# FTIR_v0_1_noCC2.net
KiCad netlist of a schematic drawn in EAGLE
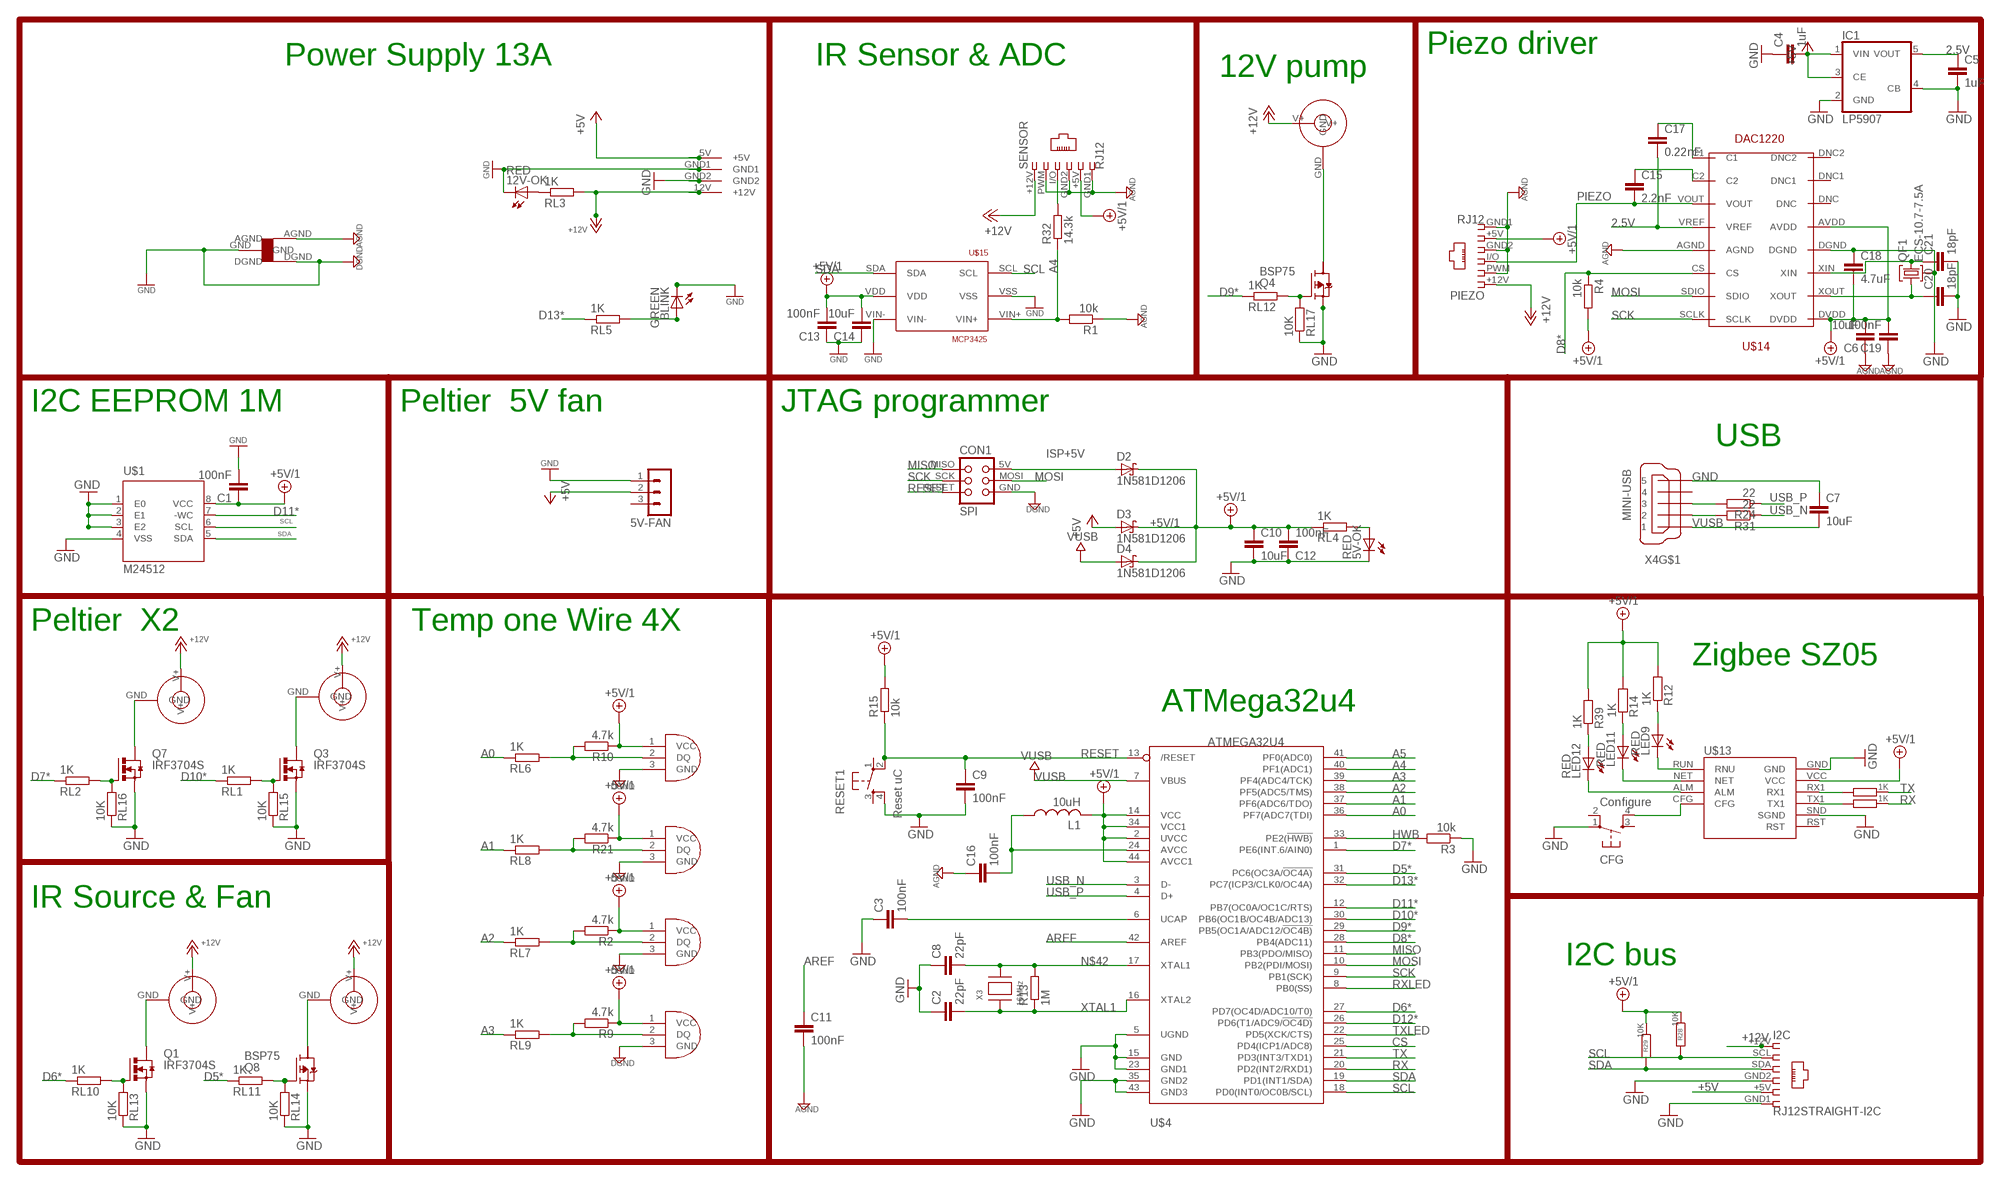
[diagram p0: schematic, sheet 1, part 1 of 2]
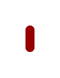
[diagram p1: schematic, sheet 1, part 2 of 2]

(export (version "E")
  (design (tool "Eeschema 10.0.6"))
  (components
    (comp (ref "5V-FAN")
      (value "MA03-1")
      (footprint "eagle-import:MA03-1")
      (libsource (lib "eagle-import") (part "MA03-1"))
    )
    (comp (ref "5V-OK")
      (value "RED")
      (footprint "eagle-import:CHIPLED_1206")
      (libsource (lib "eagle-import") (part "LEDCHIPLED_1206"))
    )
    (comp (ref "12V-OK")
      (value "RED")
      (footprint "eagle-import:CHIPLED_1206")
      (libsource (lib "eagle-import") (part "LEDCHIPLED_1206"))
    )
    (comp (ref "BLINK")
      (value "GREEN")
      (footprint "eagle-import:CHIPLED_1206")
      (libsource (lib "eagle-import") (part "LEDCHIPLED_1206"))
    )
    (comp (ref "C1")
      (value "100nF")
      (footprint "eagle-import:C1206")
      (libsource (lib "eagle-import") (part "C-EUC1206"))
    )
    (comp (ref "C2")
      (value "22pF")
      (footprint "eagle-import:C1206")
      (libsource (lib "eagle-import") (part "C-EUC1206"))
    )
    (comp (ref "C3")
      (value "100nF")
      (footprint "eagle-import:C1206")
      (libsource (lib "eagle-import") (part "C-EUC1206"))
    )
    (comp (ref "C4")
      (value "1uF")
      (footprint "eagle-import:C1206")
      (libsource (lib "eagle-import") (part "C-EUC1206"))
    )
    (comp (ref "C5")
      (value "1uF")
      (footprint "eagle-import:C1206")
      (libsource (lib "eagle-import") (part "C-EUC1206"))
    )
    (comp (ref "C6")
      (value "10uF")
      (footprint "eagle-import:C1206")
      (libsource (lib "eagle-import") (part "C-EUC1206"))
    )
    (comp (ref "C7")
      (value "10uF")
      (footprint "eagle-import:C1206")
      (libsource (lib "eagle-import") (part "C-EUC1206"))
    )
    (comp (ref "C8")
      (value "22pF")
      (footprint "eagle-import:C1206")
      (libsource (lib "eagle-import") (part "C-EUC1206"))
    )
    (comp (ref "C9")
      (value "100nF")
      (footprint "eagle-import:C1206")
      (libsource (lib "eagle-import") (part "C-EUC1206"))
    )
    (comp (ref "C10")
      (value "10uF")
      (footprint "eagle-import:C1206")
      (libsource (lib "eagle-import") (part "C-EUC1206"))
    )
    (comp (ref "C11")
      (value "100nF")
      (footprint "eagle-import:C1206")
      (libsource (lib "eagle-import") (part "C-EUC1206"))
    )
    (comp (ref "C12")
      (value "100nF")
      (footprint "eagle-import:C1206")
      (libsource (lib "eagle-import") (part "C-EUC1206"))
    )
    (comp (ref "C13")
      (value "100nF")
      (footprint "eagle-import:C1206")
      (libsource (lib "eagle-import") (part "C-EUC1206"))
    )
    (comp (ref "C14")
      (value "10uF")
      (footprint "eagle-import:C1206")
      (libsource (lib "eagle-import") (part "C-EUC1206"))
    )
    (comp (ref "C15")
      (value "2.2nF")
      (footprint "eagle-import:C1206")
      (libsource (lib "eagle-import") (part "C-EUC1206"))
    )
    (comp (ref "C16")
      (value "100nF")
      (footprint "eagle-import:C1206")
      (libsource (lib "eagle-import") (part "C-EUC1206"))
    )
    (comp (ref "C17")
      (value "0.22nF")
      (footprint "eagle-import:C1206")
      (libsource (lib "eagle-import") (part "C-EUC1206"))
    )
    (comp (ref "C18")
      (value "4.7uF")
      (footprint "eagle-import:C1206")
      (libsource (lib "eagle-import") (part "C-EUC1206"))
    )
    (comp (ref "C19")
      (value "100nF")
      (footprint "eagle-import:C1206")
      (libsource (lib "eagle-import") (part "C-EUC1206"))
    )
    (comp (ref "C20")
      (value "18pF")
      (footprint "eagle-import:C1206")
      (libsource (lib "eagle-import") (part "C-EUC1206"))
    )
    (comp (ref "C21")
      (value "18pF")
      (footprint "eagle-import:C1206")
      (libsource (lib "eagle-import") (part "C-EUC1206"))
    )
    (comp (ref "CFG")
      (value "Configure")
      (footprint "eagle-import:TACTILE_SWITCH_SMD")
      (libsource (lib "eagle-import") (part "TAC_SWITCHSMD"))
    )
    (comp (ref "CON1")
      (value "SPI")
      (footprint "eagle-import:TC2030-MCP-NL")
      (libsource (lib "eagle-import") (part "TINYISPT"))
    )
    (comp (ref "D2")
      (value "1N581D1206")
      (footprint "eagle-import:LED-1206")
      (libsource (lib "eagle-import") (part "1N581D1206"))
    )
    (comp (ref "D3")
      (value "1N581D1206")
      (footprint "eagle-import:LED-1206")
      (libsource (lib "eagle-import") (part "1N581D1206"))
    )
    (comp (ref "D4")
      (value "1N581D1206")
      (footprint "eagle-import:LED-1206")
      (libsource (lib "eagle-import") (part "1N581D1206"))
    )
    (comp (ref "I2C")
      (value "RJ12STRAIGHT-I2C")
      (footprint "eagle-import:RJ12-STRAIGHT-I2C")
      (libsource (lib "eagle-import") (part "RJ12STRAIGHT-I2C"))
    )
    (comp (ref "IC1")
      (value "LP5907")
      (footprint "eagle-import:SOT25")
      (libsource (lib "eagle-import") (part "TS520525"))
    )
    (comp (ref "L1")
      (value "10uH")
      (footprint "eagle-import:L2012C")
      (libsource (lib "eagle-import") (part "L-USL2012C"))
    )
    (comp (ref "LED9")
      (value "RED")
      (footprint "eagle-import:CHIPLED_1206")
      (libsource (lib "eagle-import") (part "LEDCHIPLED_1206"))
    )
    (comp (ref "LED11")
      (value "RED")
      (footprint "eagle-import:CHIPLED_1206")
      (libsource (lib "eagle-import") (part "LEDCHIPLED_1206"))
    )
    (comp (ref "LED12")
      (value "RED")
      (footprint "eagle-import:CHIPLED_1206")
      (libsource (lib "eagle-import") (part "LEDCHIPLED_1206"))
    )
    (comp (ref "PIEZO")
      (value "RJ12")
      (footprint "eagle-import:RJ12-STRAIGHT")
      (libsource (lib "eagle-import") (part "RJ12STRAIGHT"))
    )
    (comp (ref "Q1")
      (value "IRF3704S")
      (footprint "eagle-import:D2PACK")
      (libsource (lib "eagle-import") (part "IRF3704S"))
    )
    (comp (ref "Q3")
      (value "IRF3704S")
      (footprint "eagle-import:D2PACK")
      (libsource (lib "eagle-import") (part "IRF3704S"))
    )
    (comp (ref "Q4")
      (value "BSP75")
      (footprint "eagle-import:PG-SOT-223")
      (libsource (lib "eagle-import") (part "BSP613P"))
    )
    (comp (ref "Q7")
      (value "IRF3704S")
      (footprint "eagle-import:D2PACK")
      (libsource (lib "eagle-import") (part "IRF3704S"))
    )
    (comp (ref "Q8")
      (value "BSP75")
      (footprint "eagle-import:PG-SOT-223")
      (libsource (lib "eagle-import") (part "BSP613P"))
    )
    (comp (ref "QF1")
      (value "ECS-10.7-7.5A")
      (footprint "eagle-import:HC49U")
      (libsource (lib "eagle-import") (part "ECS-10.7-7.5A"))
    )
    (comp (ref "R1")
      (value "10k")
      (footprint "eagle-import:R0805")
      (libsource (lib "eagle-import") (part "R-EU_R0805"))
    )
    (comp (ref "R2")
      (value "4.7k")
      (footprint "eagle-import:R1206")
      (libsource (lib "eagle-import") (part "resistor_R-EU_R1206"))
    )
    (comp (ref "R3")
      (value "10k")
      (footprint "eagle-import:M0805")
      (libsource (lib "eagle-import") (part "resistor_R-EU_M0805"))
    )
    (comp (ref "R4")
      (value "10k")
      (footprint "eagle-import:R0805")
      (libsource (lib "eagle-import") (part "R-EU_R0805"))
    )
    (comp (ref "R8")
      (value "1K")
      (footprint "eagle-import:R0805")
      (libsource (lib "eagle-import") (part "R-EU_R0805"))
    )
    (comp (ref "R9")
      (value "4.7k")
      (footprint "eagle-import:R1206")
      (libsource (lib "eagle-import") (part "resistor_R-EU_R1206"))
    )
    (comp (ref "R10")
      (value "4.7k")
      (footprint "eagle-import:R1206")
      (libsource (lib "eagle-import") (part "resistor_R-EU_R1206"))
    )
    (comp (ref "R11")
      (value "1K")
      (footprint "eagle-import:R0805")
      (libsource (lib "eagle-import") (part "R-EU_R0805"))
    )
    (comp (ref "R12")
      (value "1K")
      (footprint "eagle-import:R0805")
      (libsource (lib "eagle-import") (part "R-EU_R0805"))
    )
    (comp (ref "R13")
      (value "1M")
      (footprint "eagle-import:R1206")
      (libsource (lib "eagle-import") (part "R-EU_R1206"))
    )
    (comp (ref "R14")
      (value "1K")
      (footprint "eagle-import:R0805")
      (libsource (lib "eagle-import") (part "R-EU_R0805"))
    )
    (comp (ref "R15")
      (value "10k")
      (footprint "eagle-import:M0805")
      (libsource (lib "eagle-import") (part "resistor_R-EU_M0805"))
    )
    (comp (ref "R21")
      (value "4.7k")
      (footprint "eagle-import:R1206")
      (libsource (lib "eagle-import") (part "resistor_R-EU_R1206"))
    )
    (comp (ref "R24")
      (value "22")
      (footprint "eagle-import:M1206")
      (libsource (lib "eagle-import") (part "resistor_R-EU_M1206"))
    )
    (comp (ref "R28")
      (value "10K")
      (footprint "eagle-import:M0805")
      (libsource (lib "eagle-import") (part "resistor_R-EU_M0805"))
    )
    (comp (ref "R29")
      (value "10K")
      (footprint "eagle-import:M0805")
      (libsource (lib "eagle-import") (part "resistor_R-EU_M0805"))
    )
    (comp (ref "R31")
      (value "22")
      (footprint "eagle-import:M1206")
      (libsource (lib "eagle-import") (part "resistor_R-EU_M1206"))
    )
    (comp (ref "R32")
      (value "14.3k")
      (footprint "eagle-import:R0805")
      (libsource (lib "eagle-import") (part "R-EU_R0805"))
    )
    (comp (ref "R39")
      (value "1K")
      (footprint "eagle-import:R0805")
      (libsource (lib "eagle-import") (part "R-EU_R0805"))
    )
    (comp (ref "RESET1")
      (value "Reset uC")
      (footprint "eagle-import:TACTILE_SWITCH_SMD")
      (libsource (lib "eagle-import") (part "TAC_SWITCHSMD"))
    )
    (comp (ref "RL1")
      (value "1K")
      (footprint "eagle-import:R0805")
      (libsource (lib "eagle-import") (part "R-EU_R0805"))
    )
    (comp (ref "RL2")
      (value "1K")
      (footprint "eagle-import:R0805")
      (libsource (lib "eagle-import") (part "R-EU_R0805"))
    )
    (comp (ref "RL3")
      (value "1K")
      (footprint "eagle-import:R0805")
      (libsource (lib "eagle-import") (part "R-EU_R0805"))
    )
    (comp (ref "RL4")
      (value "1K")
      (footprint "eagle-import:R0805")
      (libsource (lib "eagle-import") (part "resistor_R-EU_R0805"))
    )
    (comp (ref "RL5")
      (value "1K")
      (footprint "eagle-import:R0805")
      (libsource (lib "eagle-import") (part "R-EU_R0805"))
    )
    (comp (ref "RL6")
      (value "1K")
      (footprint "eagle-import:R0805")
      (libsource (lib "eagle-import") (part "R-EU_R0805"))
    )
    (comp (ref "RL7")
      (value "1K")
      (footprint "eagle-import:R0805")
      (libsource (lib "eagle-import") (part "R-EU_R0805"))
    )
    (comp (ref "RL8")
      (value "1K")
      (footprint "eagle-import:R0805")
      (libsource (lib "eagle-import") (part "R-EU_R0805"))
    )
    (comp (ref "RL9")
      (value "1K")
      (footprint "eagle-import:R0805")
      (libsource (lib "eagle-import") (part "R-EU_R0805"))
    )
    (comp (ref "RL10")
      (value "1K")
      (footprint "eagle-import:R0805")
      (libsource (lib "eagle-import") (part "R-EU_R0805"))
    )
    (comp (ref "RL11")
      (value "1K")
      (footprint "eagle-import:R0805")
      (libsource (lib "eagle-import") (part "R-EU_R0805"))
    )
    (comp (ref "RL12")
      (value "1K")
      (footprint "eagle-import:R0805")
      (libsource (lib "eagle-import") (part "R-EU_R0805"))
    )
    (comp (ref "RL13")
      (value "10K")
      (footprint "eagle-import:R0805")
      (libsource (lib "eagle-import") (part "R-EU_R0805"))
    )
    (comp (ref "RL14")
      (value "10K")
      (footprint "eagle-import:R0805")
      (libsource (lib "eagle-import") (part "R-EU_R0805"))
    )
    (comp (ref "RL15")
      (value "10K")
      (footprint "eagle-import:R0805")
      (libsource (lib "eagle-import") (part "R-EU_R0805"))
    )
    (comp (ref "RL16")
      (value "10K")
      (footprint "eagle-import:R0805")
      (libsource (lib "eagle-import") (part "R-EU_R0805"))
    )
    (comp (ref "RL17")
      (value "10K")
      (footprint "eagle-import:R0805")
      (libsource (lib "eagle-import") (part "R-EU_R0805"))
    )
    (comp (ref "SENSOR")
      (value "RJ12")
      (footprint "eagle-import:RJ12-STRAIGHT")
      (libsource (lib "eagle-import") (part "RJ12STRAIGHT"))
    )
    (comp (ref "U$1")
      (value "M24512")
      (footprint "eagle-import:SO8")
      (libsource (lib "eagle-import") (part "M24512"))
    )
    (comp (ref "U$3")
      (value "AMP_MATE_N_LOCK")
      (footprint "eagle-import:AMP_MATE_N_LOCK")
      (libsource (lib "eagle-import") (part "AMP_MATE_N_LOCK"))
    )
    (comp (ref "U$4")
      (value "ATMEGA32U4")
      (footprint "eagle-import:TQFP44")
      (libsource (lib "eagle-import") (part "ATMEGA32U4-AU"))
    )
    (comp (ref "U$5")
      (value "STARGND")
      (footprint "eagle-import:STAR")
      (libsource (lib "eagle-import") (part "STARGND"))
    )
    (comp (ref "U$6")
      (value "JACK_PJ-063BH")
      (footprint "eagle-import:PJ-063BH")
      (libsource (lib "eagle-import") (part "JACK_PJ-063BH"))
    )
    (comp (ref "U$9")
      (value "DS18B20_PINS")
      (footprint "eagle-import:3PINS_SMALL")
      (libsource (lib "eagle-import") (part "DS18B20_PINS"))
    )
    (comp (ref "U$10")
      (value "DS18B20_PINS")
      (footprint "eagle-import:3PINS_SMALL")
      (libsource (lib "eagle-import") (part "DS18B20_PINS"))
    )
    (comp (ref "U$11")
      (value "DS18B20_PINS")
      (footprint "eagle-import:3PINS_SMALL")
      (libsource (lib "eagle-import") (part "DS18B20_PINS"))
    )
    (comp (ref "U$12")
      (value "DS18B20_PINS")
      (footprint "eagle-import:3PINS_SMALL")
      (libsource (lib "eagle-import") (part "DS18B20_PINS"))
    )
    (comp (ref "U$13")
      (value "SZ05-ZIGBEESMD")
      (footprint "eagle-import:SZ05-ZIGBEE3")
      (libsource (lib "eagle-import") (part "SZ05-ZIGBEESMD"))
    )
    (comp (ref "U$14")
      (value "DAC1220")
      (footprint "eagle-import:SSOP-16")
      (libsource (lib "eagle-import") (part "DAC1220"))
    )
    (comp (ref "U$15")
      (value "MCP3425")
      (footprint "eagle-import:SOT-23-6")
      (libsource (lib "eagle-import") (part "MCP3425"))
    )
    (comp (ref "U$16")
      (value "JACK_PJ-063BH")
      (footprint "eagle-import:PJ-063BH")
      (libsource (lib "eagle-import") (part "JACK_PJ-063BH"))
    )
    (comp (ref "U$17")
      (value "JACK_PJ-063BH")
      (footprint "eagle-import:PJ-063BH")
      (libsource (lib "eagle-import") (part "JACK_PJ-063BH"))
    )
    (comp (ref "U$18")
      (value "JACK_PJ-063BH")
      (footprint "eagle-import:PJ-063BH")
      (libsource (lib "eagle-import") (part "JACK_PJ-063BH"))
    )
    (comp (ref "U$19")
      (value "JACK_PJ-063BH")
      (footprint "eagle-import:PJ-063BH")
      (libsource (lib "eagle-import") (part "JACK_PJ-063BH"))
    )
    (comp (ref "X3")
      (value "16MHz")
      (footprint "eagle-import:NX6035")
      (libsource (lib "eagle-import") (part "XTALNX6035"))
    )
    (comp (ref "X4")
      (value "MINI-USB")
      (footprint "eagle-import:32005-201")
      (libsource (lib "eagle-import") (part "MINI-USB-SCHIELD-32005-201"))
    )
  )
  (nets
    (net (code "1") (name "+5V") (class "Default")
      (node (ref "5V-FAN") (pin "2") (pinfunction "2_2") (pintype "passive"))
      (node (ref "C4") (pin "2") (pinfunction "2_2") (pintype "passive"))
      (node (ref "D3") (pin "A") (pinfunction "A_A") (pintype "passive"))
      (node (ref "I2C") (pin "+5V") (pinfunction "5_+5V") (pintype "bidirectional"))
      (node (ref "IC1") (pin "1") (pinfunction "VIN_1") (pintype "input"))
      (node (ref "IC1") (pin "3") (pinfunction "CE_3") (pintype "input"))
      (node (ref "U$3") (pin "5V") (pinfunction "+5V_5V") (pintype "power_in"))
    )
    (net (code "2") (name "+5V{slash}1") (class "Default")
      (node (ref "C1") (pin "1") (pinfunction "1_1") (pintype "passive"))
      (node (ref "C10") (pin "1") (pinfunction "1_1") (pintype "passive"))
      (node (ref "C12") (pin "2") (pinfunction "2_2") (pintype "passive"))
      (node (ref "C13") (pin "2") (pinfunction "2_2") (pintype "passive"))
      (node (ref "C14") (pin "2") (pinfunction "2_2") (pintype "passive"))
      (node (ref "C18") (pin "2") (pinfunction "2_2") (pintype "passive"))
      (node (ref "C19") (pin "2") (pinfunction "2_2") (pintype "passive"))
      (node (ref "C6") (pin "2") (pinfunction "2_2") (pintype "passive"))
      (node (ref "D2") (pin "C") (pinfunction "C_C") (pintype "passive"))
      (node (ref "D3") (pin "C") (pinfunction "C_C") (pintype "passive"))
      (node (ref "D4") (pin "C") (pinfunction "C_C") (pintype "passive"))
      (node (ref "L1") (pin "2") (pinfunction "2_2") (pintype "passive"))
      (node (ref "PIEZO") (pin "+5V") (pinfunction "5_+5V") (pintype "bidirectional"))
      (node (ref "R10") (pin "1") (pinfunction "1_1") (pintype "passive"))
      (node (ref "R12") (pin "2") (pinfunction "2_2") (pintype "passive"))
      (node (ref "R14") (pin "2") (pinfunction "2_2") (pintype "passive"))
      (node (ref "R15") (pin "2") (pinfunction "2_2") (pintype "passive"))
      (node (ref "R2") (pin "1") (pinfunction "1_1") (pintype "passive"))
      (node (ref "R21") (pin "1") (pinfunction "1_1") (pintype "passive"))
      (node (ref "R28") (pin "1") (pinfunction "1_1") (pintype "passive"))
      (node (ref "R29") (pin "1") (pinfunction "1_1") (pintype "passive"))
      (node (ref "R39") (pin "2") (pinfunction "2_2") (pintype "passive"))
      (node (ref "R4") (pin "2") (pinfunction "2_2") (pintype "passive"))
      (node (ref "R9") (pin "1") (pinfunction "1_1") (pintype "passive"))
      (node (ref "RL4") (pin "1") (pinfunction "1_1") (pintype "passive"))
      (node (ref "SENSOR") (pin "+5V") (pinfunction "5_+5V") (pintype "bidirectional"))
      (node (ref "U$1") (pin "8") (pinfunction "VCC_8") (pintype "power_in"))
      (node (ref "U$10") (pin "1") (pinfunction "VCC_1") (pintype "bidirectional"))
      (node (ref "U$11") (pin "1") (pinfunction "VCC_1") (pintype "bidirectional"))
      (node (ref "U$12") (pin "1") (pinfunction "VCC_1") (pintype "bidirectional"))
      (node (ref "U$13") (pin "VCC") (pinfunction "VCC_VCC") (pintype "bidirectional"))
      (node (ref "U$14") (pin "AVDD") (pinfunction "AVDD_AVDD") (pintype "bidirectional"))
      (node (ref "U$14") (pin "DVDD") (pinfunction "DVDD_DVDD") (pintype "bidirectional"))
      (node (ref "U$15") (pin "VDD") (pinfunction "VDD_VDD") (pintype "bidirectional"))
      (node (ref "U$4") (pin "14") (pinfunction "VCC_14") (pintype "bidirectional"))
      (node (ref "U$4") (pin "2") (pinfunction "UVCC_2") (pintype "bidirectional"))
      (node (ref "U$4") (pin "34") (pinfunction "VCC1_34") (pintype "bidirectional"))
      (node (ref "U$4") (pin "44") (pinfunction "AVCC1_44") (pintype "bidirectional"))
      (node (ref "U$9") (pin "1") (pinfunction "VCC_1") (pintype "bidirectional"))
    )
    (net (code "3") (name "+12V") (class "Default")
      (node (ref "I2C") (pin "+12V") (pinfunction "1_+12V") (pintype "bidirectional"))
      (node (ref "PIEZO") (pin "+12V") (pinfunction "1_+12V") (pintype "bidirectional"))
      (node (ref "RL3") (pin "2") (pinfunction "2_2") (pintype "passive"))
      (node (ref "SENSOR") (pin "+12V") (pinfunction "1_+12V") (pintype "bidirectional"))
      (node (ref "U$16") (pin "V+") (pinfunction "V+_V+") (pintype "bidirectional"))
      (node (ref "U$17") (pin "V+") (pinfunction "V+_V+") (pintype "bidirectional"))
      (node (ref "U$18") (pin "V+") (pinfunction "V+_V+") (pintype "bidirectional"))
      (node (ref "U$19") (pin "V+") (pinfunction "V+_V+") (pintype "bidirectional"))
      (node (ref "U$3") (pin "12V") (pinfunction "+12V_12V") (pintype "power_in"))
      (node (ref "U$6") (pin "V+") (pinfunction "V+_V+") (pintype "bidirectional"))
    )
    (net (code "4") (name "/2.5V") (class "Default")
      (node (ref "C17") (pin "2") (pinfunction "2_2") (pintype "passive"))
      (node (ref "C5") (pin "1") (pinfunction "1_1") (pintype "passive"))
      (node (ref "IC1") (pin "5") (pinfunction "VOUT_5") (pintype "passive"))
      (node (ref "U$14") (pin "VREF") (pinfunction "VREF_VREF") (pintype "bidirectional"))
    )
    (net (code "5") (name "/A0") (class "Default")
      (node (ref "RL6") (pin "1") (pinfunction "1_1") (pintype "passive"))
      (node (ref "U$4") (pin "36") (pinfunction "PF7(ADC7(TDI)_36") (pintype "bidirectional"))
    )
    (net (code "6") (name "/A1") (class "Default")
      (node (ref "RL8") (pin "1") (pinfunction "1_1") (pintype "passive"))
      (node (ref "U$4") (pin "37") (pinfunction "PF6(ADC6/TDO)_37") (pintype "bidirectional"))
    )
    (net (code "7") (name "/A2") (class "Default")
      (node (ref "RL7") (pin "1") (pinfunction "1_1") (pintype "passive"))
      (node (ref "U$4") (pin "38") (pinfunction "PF5(ADC5/TMS)_38") (pintype "bidirectional"))
    )
    (net (code "8") (name "/A3") (class "Default")
      (node (ref "RL9") (pin "1") (pinfunction "1_1") (pintype "passive"))
      (node (ref "U$4") (pin "39") (pinfunction "PF4(ADC4/TCK)_39") (pintype "bidirectional"))
    )
    (net (code "9") (name "/A4") (class "Default")
      (node (ref "R1") (pin "2") (pinfunction "2_2") (pintype "passive"))
      (node (ref "R32") (pin "1") (pinfunction "1_1") (pintype "passive"))
      (node (ref "U$15") (pin "VIN+") (pinfunction "VIN+_VIN+") (pintype "bidirectional"))
      (node (ref "U$4") (pin "40") (pinfunction "PF1(ADC1)_40") (pintype "bidirectional"))
    )
    (net (code "10") (name "/A5") (class "Default")
      (node (ref "U$4") (pin "41") (pinfunction "PF0(ADC0)_41") (pintype "bidirectional"))
    )
    (net (code "11") (name "/AREF") (class "Default")
      (node (ref "C11") (pin "1") (pinfunction "1_1") (pintype "passive"))
      (node (ref "U$4") (pin "42") (pinfunction "AREF_42") (pintype "bidirectional"))
    )
    (net (code "12") (name "/CS") (class "Default")
      (node (ref "U$4") (pin "25") (pinfunction "PD4(ICP1/ADC8)_25") (pintype "bidirectional"))
    )
    (net (code "13") (name "/D5*") (class "Default")
      (node (ref "RL11") (pin "1") (pinfunction "1_1") (pintype "passive"))
      (node (ref "U$4") (pin "31") (pinfunction "PC6(OC3A/~{OC4A})_31") (pintype "bidirectional"))
    )
    (net (code "14") (name "/D6*") (class "Default")
      (node (ref "RL10") (pin "1") (pinfunction "1_1") (pintype "passive"))
      (node (ref "U$4") (pin "27") (pinfunction "PD7(OC4D/ADC10/T0)_27") (pintype "bidirectional"))
    )
    (net (code "15") (name "/D7*") (class "Default")
      (node (ref "RL2") (pin "1") (pinfunction "1_1") (pintype "passive"))
      (node (ref "U$4") (pin "1") (pinfunction "PE6(INT.6/AIN0)_1") (pintype "bidirectional"))
    )
    (net (code "16") (name "/D8*") (class "Default")
      (node (ref "R4") (pin "1") (pinfunction "1_1") (pintype "passive"))
      (node (ref "U$14") (pin "CS") (pinfunction "CS_CS") (pintype "bidirectional"))
      (node (ref "U$4") (pin "28") (pinfunction "PB4(ADC11)_28") (pintype "bidirectional"))
    )
    (net (code "17") (name "/D9*") (class "Default")
      (node (ref "RL12") (pin "1") (pinfunction "1_1") (pintype "passive"))
      (node (ref "U$4") (pin "29") (pinfunction "PB5(OC1A/ADC12/~{OC4B})_29") (pintype "bidirectional"))
    )
    (net (code "18") (name "/D10*") (class "Default")
      (node (ref "RL1") (pin "1") (pinfunction "1_1") (pintype "passive"))
      (node (ref "U$4") (pin "30") (pinfunction "PB6(OC1B/OC4B/ADC13)_30") (pintype "bidirectional"))
    )
    (net (code "19") (name "/D11*") (class "Default")
      (node (ref "U$1") (pin "7") (pinfunction "-WC_7") (pintype "bidirectional"))
      (node (ref "U$4") (pin "12") (pinfunction "PB7(OC0A/OC1C/RTS)_12") (pintype "bidirectional"))
    )
    (net (code "20") (name "/D12*") (class "Default")
      (node (ref "U$4") (pin "26") (pinfunction "PD6(T1/ADC9/~{OC4D})_26") (pintype "bidirectional"))
    )
    (net (code "21") (name "/D13*") (class "Default")
      (node (ref "RL5") (pin "1") (pinfunction "1_1") (pintype "passive"))
      (node (ref "U$4") (pin "32") (pinfunction "PC7(ICP3/CLK0/OC4A)_32") (pintype "bidirectional"))
    )
    (net (code "22") (name "/HWB") (class "Default")
      (node (ref "R3") (pin "2") (pinfunction "2_2") (pintype "passive"))
      (node (ref "U$4") (pin "33") (pinfunction "PE2(~{HWB})_33") (pintype "bidirectional"))
    )
    (net (code "23") (name "/ISP+5V") (class "Default")
      (node (ref "CON1") (pin "5V") (pinfunction "VCC_5V") (pintype "passive"))
      (node (ref "D2") (pin "A") (pinfunction "A_A") (pintype "passive"))
    )
    (net (code "24") (name "/MISO") (class "Default")
      (node (ref "CON1") (pin "MISO") (pinfunction "MISO_MISO") (pintype "passive"))
      (node (ref "U$4") (pin "11") (pinfunction "PB3(PDO/MISO)_11") (pintype "bidirectional"))
    )
    (net (code "25") (name "/MOSI") (class "Default")
      (node (ref "CON1") (pin "MOSI") (pinfunction "MOSI_MOSI") (pintype "passive"))
      (node (ref "U$14") (pin "SDIO") (pinfunction "SDIO_SDIO") (pintype "bidirectional"))
      (node (ref "U$4") (pin "10") (pinfunction "PB2(PDI/MOSI)_10") (pintype "bidirectional"))
    )
    (net (code "26") (name "/N$42") (class "Default")
      (node (ref "C8") (pin "2") (pinfunction "2_2") (pintype "passive"))
      (node (ref "R13") (pin "2") (pinfunction "2_2") (pintype "passive"))
      (node (ref "U$4") (pin "17") (pinfunction "XTAL1_17") (pintype "bidirectional"))
      (node (ref "X3") (pin "P$2") (pinfunction "P$2_P$2") (pintype "bidirectional"))
    )
    (net (code "27") (name "/PIEZO") (class "Default")
      (node (ref "C15") (pin "2") (pinfunction "2_2") (pintype "passive"))
      (node (ref "PIEZO") (pin "I/O") (pinfunction "3_I/O") (pintype "bidirectional"))
      (node (ref "U$14") (pin "VOUT") (pinfunction "VOUT_VOUT") (pintype "bidirectional"))
    )
    (net (code "28") (name "/RESET") (class "Default")
      (node (ref "C9") (pin "1") (pinfunction "1_1") (pintype "passive"))
      (node (ref "CON1") (pin "RESET") (pinfunction "RESET_RESET") (pintype "passive"))
      (node (ref "R15") (pin "1") (pinfunction "1_1") (pintype "passive"))
      (node (ref "RESET1") (pin "2") (pinfunction "2_2") (pintype "passive"))
      (node (ref "U$4") (pin "13") (pinfunction "/RESET_13") (pintype "bidirectional"))
    )
    (net (code "29") (name "/RX") (class "Default")
      (node (ref "R8") (pin "1") (pinfunction "1_1") (pintype "passive"))
      (node (ref "U$4") (pin "20") (pinfunction "PD2(INT2/RXD1)_20") (pintype "bidirectional"))
    )
    (net (code "30") (name "/RXLED") (class "Default")
      (node (ref "U$4") (pin "8") (pinfunction "PB0(SS)_8") (pintype "bidirectional"))
    )
    (net (code "31") (name "/SCK") (class "Default")
      (node (ref "CON1") (pin "SCK") (pinfunction "SCK_SCK") (pintype "passive"))
      (node (ref "U$14") (pin "SCLK") (pinfunction "SCLK_SCLK") (pintype "bidirectional"))
      (node (ref "U$4") (pin "9") (pinfunction "PB1(SCK)_9") (pintype "bidirectional"))
    )
    (net (code "32") (name "/SCL") (class "Default")
      (node (ref "I2C") (pin "SCL") (pinfunction "2_SCL") (pintype "bidirectional"))
      (node (ref "R28") (pin "2") (pinfunction "2_2") (pintype "passive"))
      (node (ref "U$1") (pin "6") (pinfunction "SCL_6") (pintype "bidirectional"))
      (node (ref "U$15") (pin "SCL") (pinfunction "SCL_SCL") (pintype "bidirectional"))
      (node (ref "U$4") (pin "18") (pinfunction "PD0(INT0/OC0B/SCL)_18") (pintype "bidirectional"))
    )
    (net (code "33") (name "/SDA") (class "Default")
      (node (ref "I2C") (pin "SDA") (pinfunction "3_SDA") (pintype "bidirectional"))
      (node (ref "R29") (pin "2") (pinfunction "2_2") (pintype "passive"))
      (node (ref "U$1") (pin "5") (pinfunction "SDA_5") (pintype "bidirectional"))
      (node (ref "U$15") (pin "SDA") (pinfunction "SDA_SDA") (pintype "bidirectional"))
      (node (ref "U$4") (pin "19") (pinfunction "PD1(INT1/SDA)_19") (pintype "bidirectional"))
    )
    (net (code "34") (name "/TX") (class "Default")
      (node (ref "R11") (pin "1") (pinfunction "1_1") (pintype "passive"))
      (node (ref "U$4") (pin "21") (pinfunction "PD3(INT3/TXD1)_21") (pintype "bidirectional"))
    )
    (net (code "35") (name "/TXLED") (class "Default")
      (node (ref "U$4") (pin "22") (pinfunction "PD5(XCK/CTS)_22") (pintype "bidirectional"))
    )
    (net (code "36") (name "/USB_N") (class "Default")
      (node (ref "R31") (pin "1") (pinfunction "1_1") (pintype "passive"))
      (node (ref "U$4") (pin "3") (pinfunction "D-_3") (pintype "bidirectional"))
    )
    (net (code "37") (name "/USB_P") (class "Default")
      (node (ref "R24") (pin "1") (pinfunction "1_1") (pintype "passive"))
      (node (ref "U$4") (pin "4") (pinfunction "D+_4") (pintype "bidirectional"))
    )
    (net (code "38") (name "/XTAL1") (class "Default")
      (node (ref "C2") (pin "2") (pinfunction "2_2") (pintype "passive"))
      (node (ref "R13") (pin "1") (pinfunction "1_1") (pintype "passive"))
      (node (ref "U$4") (pin "16") (pinfunction "XTAL2_16") (pintype "bidirectional"))
      (node (ref "X3") (pin "P$1") (pinfunction "P$1_P$1") (pintype "bidirectional"))
    )
    (net (code "39") (name "AGND") (class "Default")
      (node (ref "C11") (pin "2") (pinfunction "2_2") (pintype "passive"))
      (node (ref "C16") (pin "1") (pinfunction "1_1") (pintype "passive"))
      (node (ref "C19") (pin "1") (pinfunction "1_1") (pintype "passive"))
      (node (ref "C6") (pin "1") (pinfunction "1_1") (pintype "passive"))
      (node (ref "PIEZO") (pin "GND1") (pinfunction "6_GND1") (pintype "bidirectional"))
      (node (ref "PIEZO") (pin "GND2") (pinfunction "4_GND2") (pintype "bidirectional"))
      (node (ref "PIEZO") (pin "PWM") (pinfunction "2_PWM") (pintype "bidirectional"))
      (node (ref "R1") (pin "1") (pinfunction "1_1") (pintype "passive"))
      (node (ref "SENSOR") (pin "GND1") (pinfunction "6_GND1") (pintype "bidirectional"))
      (node (ref "SENSOR") (pin "GND2") (pinfunction "4_GND2") (pintype "bidirectional"))
      (node (ref "SENSOR") (pin "PWM") (pinfunction "2_PWM") (pintype "bidirectional"))
      (node (ref "U$14") (pin "AGND") (pinfunction "AGND_AGND") (pintype "bidirectional"))
      (node (ref "U$5") (pin "AGND") (pinfunction "AGND_AGND") (pintype "output"))
    )
    (net (code "40") (name "DGND") (class "Default")
      (node (ref "12V-OK") (pin "C") (pinfunction "C_C") (pintype "passive"))
      (node (ref "5V-FAN") (pin "1") (pinfunction "1_1") (pintype "passive"))
      (node (ref "5V-OK") (pin "C") (pinfunction "C_C") (pintype "passive"))
      (node (ref "BLINK") (pin "C") (pinfunction "C_C") (pintype "passive"))
      (node (ref "C1") (pin "2") (pinfunction "2_2") (pintype "passive"))
      (node (ref "C10") (pin "2") (pinfunction "2_2") (pintype "passive"))
      (node (ref "C12") (pin "1") (pinfunction "1_1") (pintype "passive"))
      (node (ref "C13") (pin "1") (pinfunction "1_1") (pintype "passive"))
      (node (ref "C14") (pin "1") (pinfunction "1_1") (pintype "passive"))
      (node (ref "C18") (pin "1") (pinfunction "1_1") (pintype "passive"))
      (node (ref "C2") (pin "1") (pinfunction "1_1") (pintype "passive"))
      (node (ref "C20") (pin "2") (pinfunction "2_2") (pintype "passive"))
      (node (ref "C21") (pin "2") (pinfunction "2_2") (pintype "passive"))
      (node (ref "C3") (pin "1") (pinfunction "1_1") (pintype "passive"))
      (node (ref "C4") (pin "1") (pinfunction "1_1") (pintype "passive"))
      (node (ref "C5") (pin "2") (pinfunction "2_2") (pintype "passive"))
      (node (ref "C7") (pin "1") (pinfunction "1_1") (pintype "passive"))
      (node (ref "C8") (pin "1") (pinfunction "1_1") (pintype "passive"))
      (node (ref "C9") (pin "2") (pinfunction "2_2") (pintype "passive"))
      (node (ref "CFG") (pin "1") (pinfunction "1_1") (pintype "passive"))
      (node (ref "CON1") (pin "GND") (pinfunction "GND_GND") (pintype "passive"))
      (node (ref "I2C") (pin "GND1") (pinfunction "6_GND1") (pintype "bidirectional"))
      (node (ref "I2C") (pin "GND2") (pinfunction "4_GND2") (pintype "bidirectional"))
      (node (ref "IC1") (pin "2") (pinfunction "GND_2") (pintype "passive"))
      (node (ref "IC1") (pin "4") (pinfunction "CB_4") (pintype "input"))
      (node (ref "Q1") (pin "3") (pinfunction "S_3") (pintype "passive"))
      (node (ref "Q3") (pin "3") (pinfunction "S_3") (pintype "passive"))
      (node (ref "Q4") (pin "3") (pinfunction "S_3") (pintype "passive"))
      (node (ref "Q7") (pin "3") (pinfunction "S_3") (pintype "passive"))
      (node (ref "Q8") (pin "3") (pinfunction "S_3") (pintype "passive"))
      (node (ref "QF1") (pin "2") (pinfunction "2_2") (pintype "passive"))
      (node (ref "R3") (pin "1") (pinfunction "1_1") (pintype "passive"))
      (node (ref "RESET1") (pin "4") (pinfunction "4_4") (pintype "passive"))
      (node (ref "RL13") (pin "1") (pinfunction "1_1") (pintype "passive"))
      (node (ref "RL14") (pin "1") (pinfunction "1_1") (pintype "passive"))
      (node (ref "RL15") (pin "1") (pinfunction "1_1") (pintype "passive"))
      (node (ref "RL16") (pin "1") (pinfunction "1_1") (pintype "passive"))
      (node (ref "RL17") (pin "1") (pinfunction "1_1") (pintype "passive"))
      (node (ref "U$1") (pin "1") (pinfunction "E0_1") (pintype "bidirectional"))
      (node (ref "U$1") (pin "2") (pinfunction "E1_2") (pintype "bidirectional"))
      (node (ref "U$1") (pin "3") (pinfunction "E2_3") (pintype "bidirectional"))
      (node (ref "U$1") (pin "4") (pinfunction "VSS_4") (pintype "power_in"))
      (node (ref "U$10") (pin "3") (pinfunction "GND_3") (pintype "bidirectional"))
      (node (ref "U$11") (pin "3") (pinfunction "GND_3") (pintype "bidirectional"))
      (node (ref "U$12") (pin "3") (pinfunction "GND_3") (pintype "bidirectional"))
      (node (ref "U$13") (pin "GND") (pinfunction "GND_GND") (pintype "bidirectional"))
      (node (ref "U$13") (pin "SND") (pinfunction "SGND_SND") (pintype "bidirectional"))
      (node (ref "U$14") (pin "DGND") (pinfunction "DGND_DGND") (pintype "bidirectional"))
      (node (ref "U$15") (pin "VIN-") (pinfunction "VIN-_VIN-") (pintype "bidirectional"))
      (node (ref "U$15") (pin "VSS") (pinfunction "VSS_VSS") (pintype "bidirectional"))
      (node (ref "U$3") (pin "GND1") (pinfunction "GND1_GND1") (pintype "input"))
      (node (ref "U$3") (pin "GND2") (pinfunction "GND2_GND2") (pintype "input"))
      (node (ref "U$4") (pin "15") (pinfunction "GND_15") (pintype "bidirectional"))
      (node (ref "U$4") (pin "23") (pinfunction "GND1_23") (pintype "bidirectional"))
      (node (ref "U$4") (pin "35") (pinfunction "GND2_35") (pintype "bidirectional"))
      (node (ref "U$4") (pin "43") (pinfunction "GND3_43") (pintype "bidirectional"))
      (node (ref "U$4") (pin "5") (pinfunction "UGND_5") (pintype "bidirectional"))
      (node (ref "U$5") (pin "DGND") (pinfunction "DGND_DGND") (pintype "output"))
      (node (ref "U$5") (pin "GND") (pinfunction "GND_GND") (pintype "power_in"))
      (node (ref "U$9") (pin "3") (pinfunction "GND_3") (pintype "bidirectional"))
      (node (ref "X4") (pin "5") (pinfunction "5_5") (pintype "passive"))
    )
    (net (code "41") (name "Net-(5V-OK-PadA)") (class "Default")
      (node (ref "5V-OK") (pin "A") (pinfunction "A_A") (pintype "passive"))
      (node (ref "RL4") (pin "2") (pinfunction "2_2") (pintype "passive"))
    )
    (net (code "42") (name "Net-(12V-OK-PadA)") (class "Default")
      (node (ref "12V-OK") (pin "A") (pinfunction "A_A") (pintype "passive"))
      (node (ref "RL3") (pin "1") (pinfunction "1_1") (pintype "passive"))
    )
    (net (code "43") (name "Net-(BLINK-PadA)") (class "Default")
      (node (ref "BLINK") (pin "A") (pinfunction "A_A") (pintype "passive"))
      (node (ref "RL5") (pin "2") (pinfunction "2_2") (pintype "passive"))
    )
    (net (code "44") (name "Net-(C15-Pad1)") (class "Default")
      (node (ref "C15") (pin "1") (pinfunction "1_1") (pintype "passive"))
      (node (ref "U$14") (pin "C2") (pinfunction "C2_C2") (pintype "bidirectional"))
    )
    (net (code "45") (name "Net-(C17-Pad1)") (class "Default")
      (node (ref "C17") (pin "1") (pinfunction "1_1") (pintype "passive"))
      (node (ref "U$14") (pin "C1") (pinfunction "C1_C1") (pintype "bidirectional"))
    )
    (net (code "46") (name "Net-(C20-Pad1)") (class "Default")
      (node (ref "C20") (pin "1") (pinfunction "1_1") (pintype "passive"))
      (node (ref "QF1") (pin "1") (pinfunction "1_1") (pintype "passive"))
      (node (ref "U$14") (pin "XOUT") (pinfunction "XOUT_XOUT") (pintype "bidirectional"))
    )
    (net (code "47") (name "Net-(C21-Pad1)") (class "Default")
      (node (ref "C21") (pin "1") (pinfunction "1_1") (pintype "passive"))
      (node (ref "QF1") (pin "3") (pinfunction "3_3") (pintype "passive"))
      (node (ref "U$14") (pin "XIN") (pinfunction "XIN_XIN") (pintype "bidirectional"))
    )
    (net (code "48") (name "Net-(CFG-Pad4)") (class "Default")
      (node (ref "CFG") (pin "4") (pinfunction "4_4") (pintype "passive"))
      (node (ref "U$13") (pin "CFG") (pinfunction "CFG_CFG") (pintype "bidirectional"))
    )
    (net (code "49") (name "Net-(LED9-PadA)") (class "Default")
      (node (ref "LED9") (pin "A") (pinfunction "A_A") (pintype "passive"))
      (node (ref "R12") (pin "1") (pinfunction "1_1") (pintype "passive"))
    )
    (net (code "50") (name "Net-(LED11-PadA)") (class "Default")
      (node (ref "LED11") (pin "A") (pinfunction "A_A") (pintype "passive"))
      (node (ref "R14") (pin "1") (pinfunction "1_1") (pintype "passive"))
    )
    (net (code "51") (name "Net-(LED11-PadC)") (class "Default")
      (node (ref "LED11") (pin "C") (pinfunction "C_C") (pintype "passive"))
      (node (ref "U$13") (pin "NET") (pinfunction "NET_NET") (pintype "bidirectional"))
    )
    (net (code "52") (name "Net-(LED12-PadA)") (class "Default")
      (node (ref "LED12") (pin "A") (pinfunction "A_A") (pintype "passive"))
      (node (ref "R39") (pin "1") (pinfunction "1_1") (pintype "passive"))
    )
    (net (code "53") (name "Net-(LED12-PadC)") (class "Default")
      (node (ref "LED12") (pin "C") (pinfunction "C_C") (pintype "passive"))
      (node (ref "U$13") (pin "ALM") (pinfunction "ALM_ALM") (pintype "bidirectional"))
    )
    (net (code "54") (name "Net-(Q1-D)") (class "Default")
      (node (ref "Q1") (pin "2") (pinfunction "D_2") (pintype "passive"))
      (node (ref "U$17") (pin "GND") (pinfunction "GND_GND") (pintype "bidirectional"))
    )
    (net (code "55") (name "Net-(Q1-G)") (class "Default")
      (node (ref "Q1") (pin "1") (pinfunction "G_1") (pintype "passive"))
      (node (ref "RL10") (pin "2") (pinfunction "2_2") (pintype "passive"))
      (node (ref "RL13") (pin "2") (pinfunction "2_2") (pintype "passive"))
    )
    (net (code "56") (name "Net-(Q3-D)") (class "Default")
      (node (ref "Q3") (pin "2") (pinfunction "D_2") (pintype "passive"))
      (node (ref "U$16") (pin "GND") (pinfunction "GND_GND") (pintype "bidirectional"))
    )
    (net (code "57") (name "Net-(Q3-G)") (class "Default")
      (node (ref "Q3") (pin "1") (pinfunction "G_1") (pintype "passive"))
      (node (ref "RL1") (pin "2") (pinfunction "2_2") (pintype "passive"))
      (node (ref "RL15") (pin "2") (pinfunction "2_2") (pintype "passive"))
    )
    (net (code "58") (name "Net-(Q4-D-Pad2)") (class "Default")
      (node (ref "Q4") (pin "2") (pinfunction "D_2") (pintype "passive"))
      (node (ref "U$19") (pin "GND") (pinfunction "GND_GND") (pintype "bidirectional"))
    )
    (net (code "59") (name "Net-(Q4-G)") (class "Default")
      (node (ref "Q4") (pin "1") (pinfunction "G_1") (pintype "passive"))
      (node (ref "RL12") (pin "2") (pinfunction "2_2") (pintype "passive"))
      (node (ref "RL17") (pin "2") (pinfunction "2_2") (pintype "passive"))
    )
    (net (code "60") (name "Net-(Q7-D)") (class "Default")
      (node (ref "Q7") (pin "2") (pinfunction "D_2") (pintype "passive"))
      (node (ref "U$6") (pin "GND") (pinfunction "GND_GND") (pintype "bidirectional"))
    )
    (net (code "61") (name "Net-(Q7-G)") (class "Default")
      (node (ref "Q7") (pin "1") (pinfunction "G_1") (pintype "passive"))
      (node (ref "RL16") (pin "2") (pinfunction "2_2") (pintype "passive"))
      (node (ref "RL2") (pin "2") (pinfunction "2_2") (pintype "passive"))
    )
    (net (code "62") (name "Net-(Q8-D-Pad2)") (class "Default")
      (node (ref "Q8") (pin "2") (pinfunction "D_2") (pintype "passive"))
      (node (ref "U$18") (pin "GND") (pinfunction "GND_GND") (pintype "bidirectional"))
    )
    (net (code "63") (name "Net-(Q8-G)") (class "Default")
      (node (ref "Q8") (pin "1") (pinfunction "G_1") (pintype "passive"))
      (node (ref "RL11") (pin "2") (pinfunction "2_2") (pintype "passive"))
      (node (ref "RL14") (pin "2") (pinfunction "2_2") (pintype "passive"))
    )
    (net (code "64") (name "Net-(R8-Pad2)") (class "Default")
      (node (ref "R8") (pin "2") (pinfunction "2_2") (pintype "passive"))
      (node (ref "U$13") (pin "TX1") (pinfunction "TX1_TX1") (pintype "bidirectional"))
    )
    (net (code "65") (name "Net-(R11-Pad2)") (class "Default")
      (node (ref "R11") (pin "2") (pinfunction "2_2") (pintype "passive"))
      (node (ref "U$13") (pin "RX1") (pinfunction "RX1_RX1") (pintype "bidirectional"))
    )
    (net (code "66") (name "Net-(R24-Pad2)") (class "Default")
      (node (ref "R24") (pin "2") (pinfunction "2_2") (pintype "passive"))
      (node (ref "X4") (pin "3") (pinfunction "3_3") (pintype "passive"))
    )
    (net (code "67") (name "Net-(R31-Pad2)") (class "Default")
      (node (ref "R31") (pin "2") (pinfunction "2_2") (pintype "passive"))
      (node (ref "X4") (pin "2") (pinfunction "2_2") (pintype "passive"))
    )
    (net (code "68") (name "Net-(SENSOR-3)") (class "Default")
      (node (ref "R32") (pin "2") (pinfunction "2_2") (pintype "passive"))
      (node (ref "SENSOR") (pin "I/O") (pinfunction "3_I/O") (pintype "bidirectional"))
    )
    (net (code "69") (name "Net-(U$4-AVCC)") (class "Default")
      (node (ref "C16") (pin "2") (pinfunction "2_2") (pintype "passive"))
      (node (ref "L1") (pin "1") (pinfunction "1_1") (pintype "passive"))
      (node (ref "U$4") (pin "24") (pinfunction "AVCC_24") (pintype "bidirectional"))
    )
    (net (code "70") (name "Net-(U$4-UCAP)") (class "Default")
      (node (ref "C3") (pin "2") (pinfunction "2_2") (pintype "passive"))
      (node (ref "U$4") (pin "6") (pinfunction "UCAP_6") (pintype "bidirectional"))
    )
    (net (code "71") (name "Net-(U$9-DQ)") (class "Default")
      (node (ref "R10") (pin "2") (pinfunction "2_2") (pintype "passive"))
      (node (ref "RL6") (pin "2") (pinfunction "2_2") (pintype "passive"))
      (node (ref "U$9") (pin "2") (pinfunction "DQ_2") (pintype "bidirectional"))
    )
    (net (code "72") (name "Net-(U$10-DQ)") (class "Default")
      (node (ref "R21") (pin "2") (pinfunction "2_2") (pintype "passive"))
      (node (ref "RL8") (pin "2") (pinfunction "2_2") (pintype "passive"))
      (node (ref "U$10") (pin "2") (pinfunction "DQ_2") (pintype "bidirectional"))
    )
    (net (code "73") (name "Net-(U$11-DQ)") (class "Default")
      (node (ref "R2") (pin "2") (pinfunction "2_2") (pintype "passive"))
      (node (ref "RL7") (pin "2") (pinfunction "2_2") (pintype "passive"))
      (node (ref "U$11") (pin "2") (pinfunction "DQ_2") (pintype "bidirectional"))
    )
    (net (code "74") (name "Net-(U$12-DQ)") (class "Default")
      (node (ref "R9") (pin "2") (pinfunction "2_2") (pintype "passive"))
      (node (ref "RL9") (pin "2") (pinfunction "2_2") (pintype "passive"))
      (node (ref "U$12") (pin "2") (pinfunction "DQ_2") (pintype "bidirectional"))
    )
    (net (code "75") (name "Net-(U$13-RNU)") (class "Default")
      (node (ref "LED9") (pin "C") (pinfunction "C_C") (pintype "passive"))
      (node (ref "U$13") (pin "RUN") (pinfunction "RNU_RUN") (pintype "bidirectional"))
    )
    (net (code "76") (name "VUSB") (class "Default")
      (node (ref "C7") (pin "2") (pinfunction "2_2") (pintype "passive"))
      (node (ref "D4") (pin "A") (pinfunction "A_A") (pintype "passive"))
      (node (ref "U$4") (pin "7") (pinfunction "VBUS_7") (pintype "bidirectional"))
      (node (ref "X4") (pin "1") (pinfunction "1_1") (pintype "passive"))
    )
    (net (code "77") (name "unconnected-(5V-FAN-Pad3)") (class "Default")
      (node (ref "5V-FAN") (pin "3") (pinfunction "3_3") (pintype "passive"))
    )
    (net (code "78") (name "unconnected-(CFG-Pad2)") (class "Default")
      (node (ref "CFG") (pin "2") (pinfunction "2_2") (pintype "passive"))
    )
    (net (code "79") (name "unconnected-(CFG-Pad3)") (class "Default")
      (node (ref "CFG") (pin "3") (pinfunction "3_3") (pintype "passive"))
    )
    (net (code "80") (name "unconnected-(Q4-D-Pad4)") (class "Default")
      (node (ref "Q4") (pin "4") (pinfunction "D_4") (pintype "passive"))
    )
    (net (code "81") (name "unconnected-(Q8-D-Pad4)") (class "Default")
      (node (ref "Q8") (pin "4") (pinfunction "D_4") (pintype "passive"))
    )
    (net (code "82") (name "unconnected-(RESET1-Pad1)") (class "Default")
      (node (ref "RESET1") (pin "1") (pinfunction "1_1") (pintype "passive"))
    )
    (net (code "83") (name "unconnected-(RESET1-Pad3)") (class "Default")
      (node (ref "RESET1") (pin "3") (pinfunction "3_3") (pintype "passive"))
    )
    (net (code "84") (name "unconnected-(U$13-PadRST)") (class "Default")
      (node (ref "U$13") (pin "RST") (pinfunction "RST_RST") (pintype "bidirectional"))
    )
    (net (code "85") (name "unconnected-(U$14-PadDNC)") (class "Default")
      (node (ref "U$14") (pin "DNC") (pinfunction "DNC_DNC") (pintype "bidirectional"))
    )
    (net (code "86") (name "unconnected-(U$14-PadDNC1)") (class "Default")
      (node (ref "U$14") (pin "DNC1") (pinfunction "DNC1_DNC1") (pintype "bidirectional"))
    )
    (net (code "87") (name "unconnected-(U$14-PadDNC2)") (class "Default")
      (node (ref "U$14") (pin "DNC2") (pinfunction "DNC2_DNC2") (pintype "bidirectional"))
    )
    (net (code "88") (name "unconnected-(X4-Pad4)") (class "Default")
      (node (ref "X4") (pin "4") (pinfunction "4_4") (pintype "passive"))
    )
  )
)
